# Sheet1.net
KiCad netlist of a schematic drawn in Altium Designer
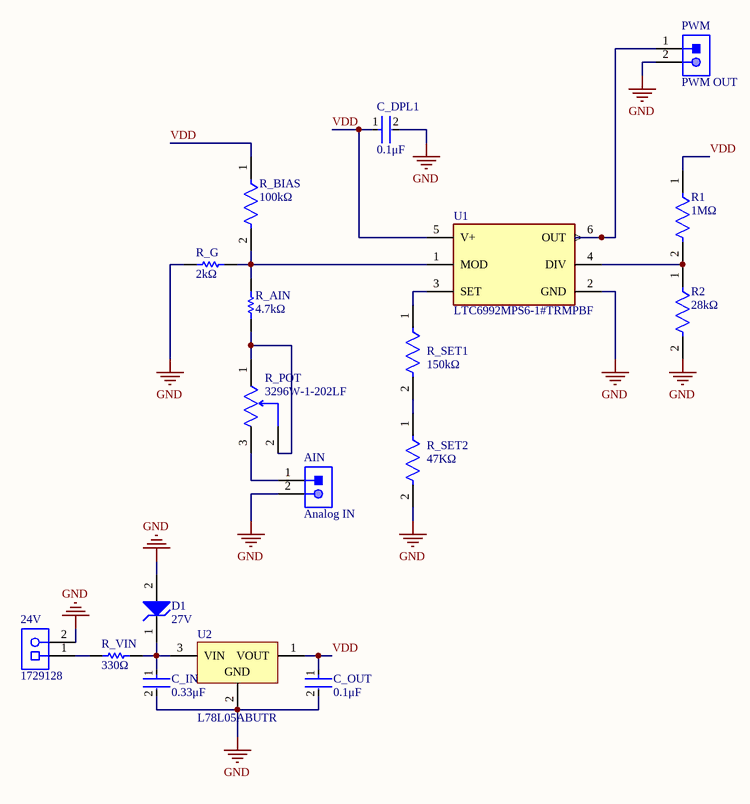
[diagram p0: Sheet1.SchDoc]

(export (version "E")
  (design (tool "Eeschema 10.0.6"))
  (components
    (comp (ref "24V")
      (value "1729128")
      (footprint "PHOE-1729128-2_V")
      (description "PCB Terminal Block, 13.5 A, 400 V, 2-Pin THD, RoHS, Bulk")
      (fields (field (name "MANUFACTURER") "Phoenix Contact"))
      (libsource (lib "Altium Content Vault") (part "CN-2P-F-R2"))
    )
    (comp (ref "AIN")
      (value "Analog IN")
      (footprint "JST-S2B-XH-A(LF)(SN)_V")
      (fields (field (name "TOLERANCE") "10%"))
      (libsource (lib "Altium Content Vault") (part "CN-1P-M-R2"))
    )
    (comp (ref "C_DPL1")
      (value "0.1μF")
      (footprint "FP-GCM21B-0_15-MFG")
      (description "Ceramic Capacitor for Automotive 100nF ±10% 100VDC X7R 0805 Embossed T/R")
      (fields (field (name "TOLERANCE") "10%") (field (name "VOLTAGE") "100V"))
      (libsource (lib "Altium Content Vault") (part "02cd4be3c70576c341d710602a673aa"))
    )
    (comp (ref "C_IN")
      (value "0.33μF")
      (footprint "FP-GCM219-0_15-MFG")
      (description "Ceramic Capacitor for Automotive 330nF  ±10% 50VDC X7R 0805 Paper T/R")
      (fields (field (name "TOLERANCE") "10%"))
      (libsource (lib "Altium Content Vault") (part "11868f565c42a9108669ba33697ecf6"))
    )
    (comp (ref "C_OUT")
      (value "0.1μF")
      (footprint "FP-GCM21B-0_15-MFG")
      (description "Ceramic Capacitor for Automotive 100nF ±10% 100VDC X7R 0805 Embossed T/R")
      (fields (field (name "TOLERANCE") "10%") (field (name "VOLTAGE") "100V"))
      (libsource (lib "Altium Content Vault") (part "02cd4be3c70576c341d710602a673aa"))
    )
    (comp (ref "D1")
      (value "27V")
      (footprint "ONSC-POWERMITE-2-457-04_D_V")
      (description "3.2 W Plastic Surface Mount, 2-Pin POWERMITE, Pb-Free, Tape and Reel")
      (fields (field (name "MANUFACTURER") "On Semiconductor") (field (name "PARTNUMBER") "1PMT5935BT1G"))
      (libsource (lib "Altium Content Vault") (part "ONSC-K1A2-2"))
    )
    (comp (ref "PWM")
      (value "PWM OUT")
      (footprint "JST-S2B-XH-A(LF)(SN)_V")
      (fields (field (name "TOLERANCE") "10%"))
      (libsource (lib "Altium Content Vault") (part "CN-1P-M-R2"))
    )
    (comp (ref "R1")
      (value "1MΩ")
      (footprint "FP-RG2012-MFG")
      (description "Automotive Metal Thin Film Chip Resistor, 0805, 1MΩ, 0.1%, 25ppm/°C, 0.125W, 150V")
      (fields (field (name "TOLERANCE") "0.1%"))
      (libsource (lib "Altium Content Vault") (part "1029c3af85768c4190bb7ad29bc67b5"))
    )
    (comp (ref "R2")
      (value "28kΩ")
      (footprint "FP-RG2012-MFG")
      (description "Automotive Metal Thin Film Chip Resistor, 0805, 280kΩ, 0.1%, 25ppm/°C, 0.125W, 150V")
      (fields (field (name "TOLERANCE") "0.1%"))
      (libsource (lib "Altium Content Vault") (part "1029c3af85768c4190bb7ad29bc67b5"))
    )
    (comp (ref "R_AIN")
      (value "4.7kΩ")
      (footprint "RESC2013X60X40ML20T25")
      (fields (field (name "PART NUMBER") "ERA6AEB472V") (field (name "MANUFACTURER") "Panasonic"))
      (libsource (lib "Altium Content Vault") (part "RES"))
    )
    (comp (ref "R_BIAS")
      (value "100kΩ")
      (footprint "FP-ERA6A-IPC_B")
      (description "RES 100K OHM 0.1% 1/8W 0805")
      (fields (field (name "TOLERANCE") "0.1%"))
      (libsource (lib "Altium Content Vault") (part "1029c3af85768c4190bb7ad29bc67b5"))
    )
    (comp (ref "R_G")
      (value "2kΩ")
      (footprint "RESC2013X60X40ML20T25")
      (fields (field (name "PART NUMBER") "ERA6AEB202V") (field (name "MANUFACTURER") "Panasonic"))
      (libsource (lib "Altium Content Vault") (part "RES"))
    )
    (comp (ref "R_POT")
      (value "3296W-1-202LF")
      (footprint "FP-3296W-MFG")
      (description "TRIMMER 2K OHM 0.5W PC PIN TOP")
      (fields (field (name "TOLERANCE") "10%"))
      (libsource (lib "Altium Content Vault") (part "81a8d1f2e6c155a1fa928b358d1a42a"))
    )
    (comp (ref "R_SET1")
      (value "150kΩ")
      (footprint "FP-ERA6A-MFG")
      (description "RES 150K OHM 0.1% 1/8W 0805")
      (fields (field (name "TOLERANCE") "0.1%"))
      (libsource (lib "Altium Content Vault") (part "1029c3af85768c4190bb7ad29bc67b5"))
    )
    (comp (ref "R_SET2")
      (value "47KΩ")
      (footprint "FP-ERA6A-MFG")
      (fields (field (name "TOLERANCE") "0.1%"))
      (libsource (lib "Altium Content Vault") (part "1029c3af85768c4190bb7ad29bc67b5"))
    )
    (comp (ref "R_VIN")
      (value "330Ω")
      (footprint "RESC2013X60X40LL20T25")
      (fields (field (name "MANUFACTURER") "Panasonic") (field (name "PART NUMBER") "ERA6AEB331V"))
      (libsource (lib "Altium Content Vault") (part "RES"))
    )
    (comp (ref "U1")
      (value "LTC6992MPS6-1#TRMPBF")
      (footprint "FP-S6-6-05-08-1636-IPC_B")
      (description "IC OSC SILICON PROG TSOT23-6")
      (libsource (lib "Altium Content Vault") (part "8a48498f8010dc692cf6b2ba4f9d0e7"))
    )
    (comp (ref "U2")
      (value "L78L05ABUTR")
      (footprint "SOT-89_N")
      (description "Positive Voltage Regulator, 5V, 4-Pin SOT-89, Tape and Reel")
      (libsource (lib "Altium Content Vault") (part "PM-REG-7805-SIL3"))
    )
  )
  (nets
    (net (code "1") (name "/VDD") (class "Default")
      (node (ref "C_DPL1") (pin "1") (pinfunction "1_1") (pintype "passive"))
      (node (ref "C_OUT") (pin "1") (pinfunction "1_1") (pintype "passive"))
      (node (ref "R1") (pin "1") (pinfunction "1_1") (pintype "passive"))
      (node (ref "R_BIAS") (pin "1") (pinfunction "1_1") (pintype "passive"))
      (node (ref "U1") (pin "5") (pinfunction "V+_5") (pintype "power_in"))
      (node (ref "U2") (pin "1") (pinfunction "VOUT_1") (pintype "power_in"))
    )
    (net (code "2") (name "GND") (class "Default")
      (node (ref "24V") (pin "2") (pinfunction "2_2") (pintype "passive"))
      (node (ref "AIN") (pin "2") (pinfunction "2_2") (pintype "passive"))
      (node (ref "C_DPL1") (pin "2") (pinfunction "2_2") (pintype "passive"))
      (node (ref "C_IN") (pin "2") (pinfunction "2_2") (pintype "passive"))
      (node (ref "C_OUT") (pin "2") (pinfunction "2_2") (pintype "passive"))
      (node (ref "D1") (pin "2") (pinfunction "A_2") (pintype "passive"))
      (node (ref "PWM") (pin "2") (pinfunction "2_2") (pintype "passive"))
      (node (ref "R2") (pin "2") (pinfunction "2_2") (pintype "passive"))
      (node (ref "R_G") (pin "1") (pinfunction "1_1") (pintype "passive"))
      (node (ref "R_SET2") (pin "2") (pinfunction "2_2") (pintype "passive"))
      (node (ref "U1") (pin "2") (pinfunction "GND_2") (pintype "power_in"))
      (node (ref "U2") (pin "2") (pinfunction "GND_2") (pintype "power_in"))
    )
    (net (code "3") (name "Net-(24V-Pad1)") (class "Default")
      (node (ref "24V") (pin "1") (pinfunction "1_1") (pintype "passive"))
      (node (ref "R_VIN") (pin "1") (pinfunction "1_1") (pintype "passive"))
    )
    (net (code "4") (name "Net-(D1-K)") (class "Default")
      (node (ref "C_IN") (pin "1") (pinfunction "1_1") (pintype "passive"))
      (node (ref "D1") (pin "1") (pinfunction "K_1") (pintype "passive"))
      (node (ref "R_VIN") (pin "2") (pinfunction "2_2") (pintype "passive"))
      (node (ref "U2") (pin "3") (pinfunction "VIN_3") (pintype "power_in"))
    )
    (net (code "5") (name "Net-(R_POT-CCW)") (class "Default")
      (node (ref "R_AIN") (pin "1") (pinfunction "1_1") (pintype "passive"))
      (node (ref "R_POT") (pin "1") (pinfunction "CCW_1") (pintype "passive"))
      (node (ref "R_POT") (pin "2") (pinfunction "WIPER_2") (pintype "passive"))
    )
    (net (code "6") (name "Net-(R_POT-CW)") (class "Default")
      (node (ref "AIN") (pin "1") (pinfunction "1_1") (pintype "passive"))
      (node (ref "R_POT") (pin "3") (pinfunction "CW_3") (pintype "passive"))
    )
    (net (code "7") (name "Net-(R_SET1-Pad2)") (class "Default")
      (node (ref "R_SET1") (pin "2") (pinfunction "2_2") (pintype "passive"))
      (node (ref "R_SET2") (pin "1") (pinfunction "1_1") (pintype "passive"))
    )
    (net (code "8") (name "Net-(U1-DIV)") (class "Default")
      (node (ref "R1") (pin "2") (pinfunction "2_2") (pintype "passive"))
      (node (ref "R2") (pin "1") (pinfunction "1_1") (pintype "passive"))
      (node (ref "U1") (pin "4") (pinfunction "DIV_4") (pintype "passive"))
    )
    (net (code "9") (name "Net-(U1-MOD)") (class "Default")
      (node (ref "R_AIN") (pin "2") (pinfunction "2_2") (pintype "passive"))
      (node (ref "R_BIAS") (pin "2") (pinfunction "2_2") (pintype "passive"))
      (node (ref "R_G") (pin "2") (pinfunction "2_2") (pintype "passive"))
      (node (ref "U1") (pin "1") (pinfunction "MOD_1") (pintype "passive"))
    )
    (net (code "10") (name "Net-(U1-OUT)") (class "Default")
      (node (ref "PWM") (pin "1") (pinfunction "1_1") (pintype "passive"))
      (node (ref "U1") (pin "6") (pinfunction "OUT_6") (pintype "output"))
    )
    (net (code "11") (name "Net-(U1-SET)") (class "Default")
      (node (ref "R_SET1") (pin "1") (pinfunction "1_1") (pintype "passive"))
      (node (ref "U1") (pin "3") (pinfunction "SET_3") (pintype "passive"))
    )
  )
)
